# neonred-coded-update-2026-10-06.net
KiCad netlist of a schematic drawn in EasyEDA
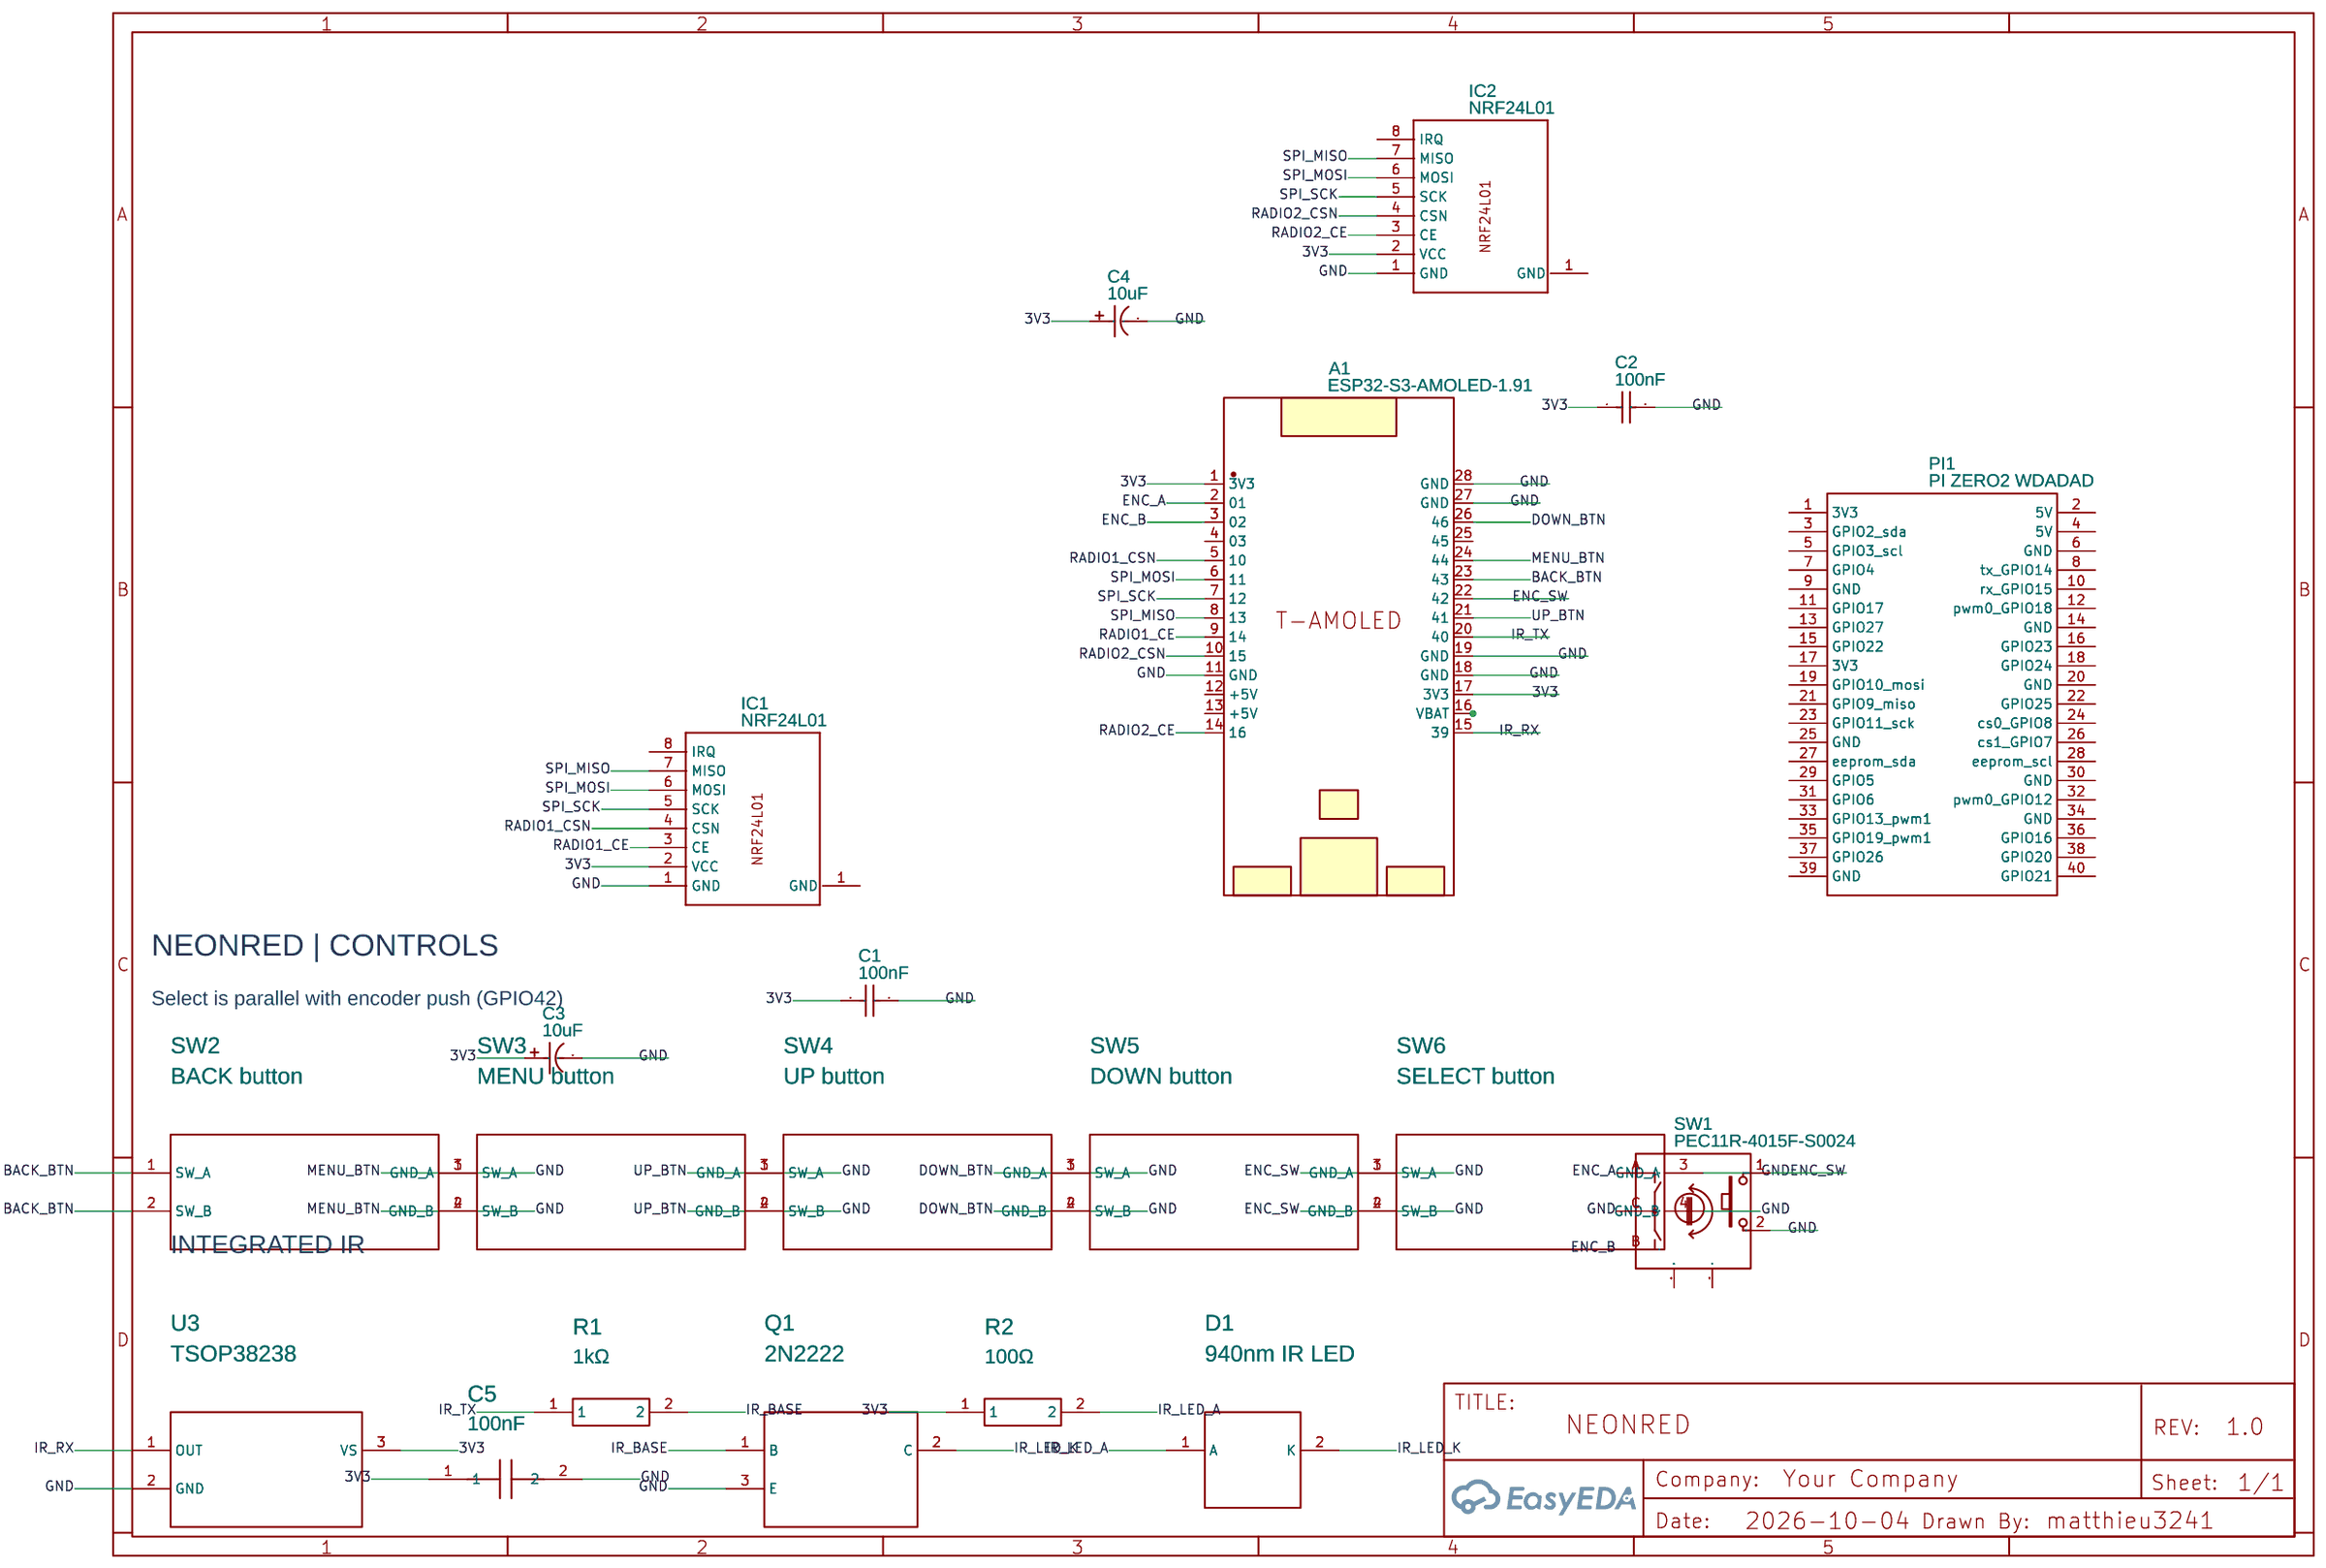
[diagram p0: schematic sheet]

(export (version "E")
  (design (tool "Eeschema 10.0.6"))
  (components
    (comp (ref "A1")
      (value "ESP32-S3-AMOLED-1.91")
      (fields (field (name "Manufacturer Part") "T-Display S3 AMOLED") (field (name "Manufacturer") "Lilygo"))
      (libsource (lib "") (part "ESP32-S3-AMOLED-1.91"))
    )
    (comp (ref "C1")
      (value "100nF")
      (fields (field (name "Manufacturer Part") "0.1UF(104) +-20% 63v"))
      (libsource (lib "") (part "100nF"))
    )
    (comp (ref "C2")
      (value "100nF")
      (fields (field (name "Manufacturer Part") "0.1UF(104) +-20% 63v"))
      (libsource (lib "") (part "100nF"))
    )
    (comp (ref "C3") (value "10uF") (libsource (lib "") (part "Capacitor 10uF TH")))
    (comp (ref "C4") (value "10uF") (libsource (lib "") (part "Capacitor 10uF TH")))
    (comp (ref "C5")
      (value "100nF")
      (fields (field (name "Manufacturer Part") "100nF ceramic THT"))
      (libsource (lib "") (part "100nF_1"))
    )
    (comp (ref "D1")
      (value "940nm IR LED")
      (fields (field (name "Manufacturer Part") "940nm IR LED, 5 mm THT"))
      (libsource (lib "") (part "940nm IR LED"))
    )
    (comp (ref "IC1") (value "NRF24L01") (libsource (lib "") (part "NRF24L01")))
    (comp (ref "IC2") (value "NRF24L01") (libsource (lib "") (part "NRF24L01")))
    (comp (ref "PI1") (value "PI ZERO2 WDADAD") (libsource (lib "") (part "PI ZERO2 WDADAD")))
    (comp (ref "Q1")
      (value "2N2222")
      (fields (field (name "Manufacturer Part") "2N2222A"))
      (libsource (lib "") (part "2N2222"))
    )
    (comp (ref "R1")
      (value "1kΩ")
      (fields (field (name "Manufacturer Part") "1k axial THT"))
      (libsource (lib "") (part "1kΩ"))
    )
    (comp (ref "R2")
      (value "100Ω")
      (fields (field (name "Manufacturer Part") "100Ω axial THT"))
      (libsource (lib "") (part "100Ω"))
    )
    (comp (ref "SW1")
      (value "PEC11R-4015F-S0024")
      (fields (field (name "Manufacturer") "BOURNS"))
      (libsource (lib "") (part "PEC11R-4015F-S0024"))
    )
    (comp (ref "SW2")
      (value "BACK button")
      (fields (field (name "Manufacturer Part") "6x6mm THT tactile switch, NO"))
      (libsource (lib "") (part "BACK button"))
    )
    (comp (ref "SW3")
      (value "MENU button")
      (fields (field (name "Manufacturer Part") "6x6mm THT tactile switch, NO"))
      (libsource (lib "") (part "MENU button"))
    )
    (comp (ref "SW4")
      (value "UP button")
      (fields (field (name "Manufacturer Part") "6x6mm THT tactile switch, NO"))
      (libsource (lib "") (part "UP button"))
    )
    (comp (ref "SW5")
      (value "DOWN button")
      (fields (field (name "Manufacturer Part") "6x6mm THT tactile switch, NO"))
      (libsource (lib "") (part "DOWN button"))
    )
    (comp (ref "SW6")
      (value "SELECT button")
      (fields (field (name "Manufacturer Part") "6x6mm THT tactile switch, NO"))
      (libsource (lib "") (part "SELECT button"))
    )
    (comp (ref "U3") (value "TSOP38238") (libsource (lib "") (part "TSOP38238")))
  )
  (nets
    (net (code "1") (name "/3V3") (class "Default")
      (node (ref "A1") (pin "1") (pinfunction "3V3_1") (pintype "unspecified"))
      (node (ref "A1") (pin "17") (pinfunction "3V3_17") (pintype "unspecified"))
      (node (ref "C1") (pin "1") (pinfunction "1_1") (pintype "input"))
      (node (ref "C2") (pin "1") (pinfunction "1_1") (pintype "input"))
      (node (ref "C3") (pin "1") (pinfunction "1_1") (pintype "input"))
      (node (ref "C4") (pin "1") (pinfunction "1_1") (pintype "input"))
      (node (ref "C5") (pin "1") (pinfunction "1_1") (pintype "unspecified"))
      (node (ref "IC1") (pin "2") (pinfunction "VCC_2") (pintype "bidirectional"))
      (node (ref "IC2") (pin "2") (pinfunction "VCC_2") (pintype "bidirectional"))
      (node (ref "R2") (pin "1") (pinfunction "1_1") (pintype "unspecified"))
      (node (ref "U3") (pin "3") (pinfunction "VS_3") (pintype "unspecified"))
    )
    (net (code "2") (name "/BACK_BTN") (class "Default")
      (node (ref "A1") (pin "23") (pinfunction "43_23") (pintype "unspecified"))
      (node (ref "SW2") (pin "1") (pinfunction "SW_A_1") (pintype "unspecified"))
      (node (ref "SW2") (pin "2") (pinfunction "SW_B_2") (pintype "unspecified"))
    )
    (net (code "3") (name "/DOWN_BTN") (class "Default")
      (node (ref "A1") (pin "26") (pinfunction "46_26") (pintype "unspecified"))
      (node (ref "SW5") (pin "1") (pinfunction "SW_A_1") (pintype "unspecified"))
      (node (ref "SW5") (pin "2") (pinfunction "SW_B_2") (pintype "unspecified"))
    )
    (net (code "4") (name "/ENC_A") (class "Default")
      (node (ref "A1") (pin "2") (pinfunction "01_2") (pintype "unspecified"))
      (node (ref "SW1") (pin "A") (pinfunction "A_A") (pintype "unspecified"))
    )
    (net (code "5") (name "/ENC_B") (class "Default")
      (node (ref "A1") (pin "3") (pinfunction "02_3") (pintype "unspecified"))
      (node (ref "SW1") (pin "B") (pinfunction "B_B") (pintype "unspecified"))
    )
    (net (code "6") (name "/ENC_SW") (class "Default")
      (node (ref "A1") (pin "22") (pinfunction "42_22") (pintype "unspecified"))
      (node (ref "SW1") (pin "1") (pinfunction "1_1") (pintype "unspecified"))
      (node (ref "SW6") (pin "1") (pinfunction "SW_A_1") (pintype "unspecified"))
      (node (ref "SW6") (pin "2") (pinfunction "SW_B_2") (pintype "unspecified"))
    )
    (net (code "7") (name "/GND") (class "Default")
      (node (ref "A1") (pin "11") (pinfunction "GND_11") (pintype "unspecified"))
      (node (ref "A1") (pin "18") (pinfunction "GND_18") (pintype "unspecified"))
      (node (ref "A1") (pin "19") (pinfunction "GND_19") (pintype "unspecified"))
      (node (ref "A1") (pin "27") (pinfunction "GND_27") (pintype "unspecified"))
      (node (ref "A1") (pin "28") (pinfunction "GND_28") (pintype "unspecified"))
      (node (ref "C1") (pin "2") (pinfunction "2_2") (pintype "input"))
      (node (ref "C2") (pin "2") (pinfunction "2_2") (pintype "input"))
      (node (ref "C3") (pin "2") (pinfunction "2_2") (pintype "input"))
      (node (ref "C4") (pin "2") (pinfunction "2_2") (pintype "input"))
      (node (ref "C5") (pin "2") (pinfunction "2_2") (pintype "unspecified"))
      (node (ref "IC1") (pin "1") (pinfunction "GND_1") (pintype "bidirectional"))
      (node (ref "IC2") (pin "1") (pinfunction "GND_1") (pintype "bidirectional"))
      (node (ref "Q1") (pin "3") (pinfunction "E_3") (pintype "unspecified"))
      (node (ref "SW1") (pin "2") (pinfunction "2_2") (pintype "unspecified"))
      (node (ref "SW1") (pin "C") (pinfunction "C_C") (pintype "unspecified"))
      (node (ref "SW2") (pin "3") (pinfunction "GND_A_3") (pintype "unspecified"))
      (node (ref "SW2") (pin "4") (pinfunction "GND_B_4") (pintype "unspecified"))
      (node (ref "SW3") (pin "3") (pinfunction "GND_A_3") (pintype "unspecified"))
      (node (ref "SW3") (pin "4") (pinfunction "GND_B_4") (pintype "unspecified"))
      (node (ref "SW4") (pin "3") (pinfunction "GND_A_3") (pintype "unspecified"))
      (node (ref "SW4") (pin "4") (pinfunction "GND_B_4") (pintype "unspecified"))
      (node (ref "SW5") (pin "3") (pinfunction "GND_A_3") (pintype "unspecified"))
      (node (ref "SW5") (pin "4") (pinfunction "GND_B_4") (pintype "unspecified"))
      (node (ref "SW6") (pin "3") (pinfunction "GND_A_3") (pintype "unspecified"))
      (node (ref "SW6") (pin "4") (pinfunction "GND_B_4") (pintype "unspecified"))
      (node (ref "U3") (pin "2") (pinfunction "GND_2") (pintype "unspecified"))
    )
    (net (code "8") (name "/IR_BASE") (class "Default")
      (node (ref "Q1") (pin "1") (pinfunction "B_1") (pintype "unspecified"))
      (node (ref "R1") (pin "2") (pinfunction "2_2") (pintype "unspecified"))
    )
    (net (code "9") (name "/IR_LED_A") (class "Default")
      (node (ref "D1") (pin "1") (pinfunction "A_1") (pintype "unspecified"))
      (node (ref "R2") (pin "2") (pinfunction "2_2") (pintype "unspecified"))
    )
    (net (code "10") (name "/IR_LED_K") (class "Default")
      (node (ref "D1") (pin "2") (pinfunction "K_2") (pintype "unspecified"))
      (node (ref "Q1") (pin "2") (pinfunction "C_2") (pintype "unspecified"))
    )
    (net (code "11") (name "/IR_RX") (class "Default")
      (node (ref "A1") (pin "15") (pinfunction "39_15") (pintype "unspecified"))
      (node (ref "U3") (pin "1") (pinfunction "OUT_1") (pintype "unspecified"))
    )
    (net (code "12") (name "/IR_TX") (class "Default")
      (node (ref "A1") (pin "20") (pinfunction "40_20") (pintype "unspecified"))
      (node (ref "R1") (pin "1") (pinfunction "1_1") (pintype "unspecified"))
    )
    (net (code "13") (name "/MENU_BTN") (class "Default")
      (node (ref "A1") (pin "24") (pinfunction "44_24") (pintype "unspecified"))
      (node (ref "SW3") (pin "1") (pinfunction "SW_A_1") (pintype "unspecified"))
      (node (ref "SW3") (pin "2") (pinfunction "SW_B_2") (pintype "unspecified"))
    )
    (net (code "14") (name "/RADIO1_CE") (class "Default")
      (node (ref "A1") (pin "9") (pinfunction "14_9") (pintype "unspecified"))
      (node (ref "IC1") (pin "3") (pinfunction "CE_3") (pintype "bidirectional"))
    )
    (net (code "15") (name "/RADIO1_CSN") (class "Default")
      (node (ref "A1") (pin "5") (pinfunction "10_5") (pintype "unspecified"))
      (node (ref "IC1") (pin "4") (pinfunction "CSN_4") (pintype "bidirectional"))
    )
    (net (code "16") (name "/RADIO2_CE") (class "Default")
      (node (ref "A1") (pin "14") (pinfunction "16_14") (pintype "unspecified"))
      (node (ref "IC2") (pin "3") (pinfunction "CE_3") (pintype "bidirectional"))
    )
    (net (code "17") (name "/RADIO2_CSN") (class "Default")
      (node (ref "A1") (pin "10") (pinfunction "15_10") (pintype "unspecified"))
      (node (ref "IC2") (pin "4") (pinfunction "CSN_4") (pintype "bidirectional"))
    )
    (net (code "18") (name "/SPI_MISO") (class "Default")
      (node (ref "A1") (pin "8") (pinfunction "13_8") (pintype "unspecified"))
      (node (ref "IC1") (pin "7") (pinfunction "MISO_7") (pintype "bidirectional"))
      (node (ref "IC2") (pin "7") (pinfunction "MISO_7") (pintype "bidirectional"))
    )
    (net (code "19") (name "/SPI_MOSI") (class "Default")
      (node (ref "A1") (pin "6") (pinfunction "11_6") (pintype "unspecified"))
      (node (ref "IC1") (pin "6") (pinfunction "MOSI_6") (pintype "bidirectional"))
      (node (ref "IC2") (pin "6") (pinfunction "MOSI_6") (pintype "bidirectional"))
    )
    (net (code "20") (name "/SPI_SCK") (class "Default")
      (node (ref "A1") (pin "7") (pinfunction "12_7") (pintype "unspecified"))
      (node (ref "IC1") (pin "5") (pinfunction "SCK_5") (pintype "bidirectional"))
      (node (ref "IC2") (pin "5") (pinfunction "SCK_5") (pintype "bidirectional"))
    )
    (net (code "21") (name "/UP_BTN") (class "Default")
      (node (ref "A1") (pin "21") (pinfunction "41_21") (pintype "unspecified"))
      (node (ref "SW4") (pin "1") (pinfunction "SW_A_1") (pintype "unspecified"))
      (node (ref "SW4") (pin "2") (pinfunction "SW_B_2") (pintype "unspecified"))
    )
    (net (code "22") (name "unconnected-(A1-+5V-Pad12)") (class "Default")
      (node (ref "A1") (pin "12") (pinfunction "+5V_12") (pintype "unspecified"))
    )
    (net (code "23") (name "unconnected-(A1-+5V-Pad13)") (class "Default")
      (node (ref "A1") (pin "13") (pinfunction "+5V_13") (pintype "unspecified"))
    )
    (net (code "24") (name "unconnected-(A1-03-Pad4)") (class "Default")
      (node (ref "A1") (pin "4") (pinfunction "03_4") (pintype "unspecified"))
    )
    (net (code "25") (name "unconnected-(A1-45-Pad25)") (class "Default")
      (node (ref "A1") (pin "25") (pinfunction "45_25") (pintype "unspecified"))
    )
    (net (code "26") (name "unconnected-(A1-VBAT-Pad16)") (class "Default")
      (node (ref "A1") (pin "16") (pinfunction "VBAT_16") (pintype "unspecified"))
    )
    (net (code "27") (name "unconnected-(IC1-GND-Pad1)") (class "Default")
      (node (ref "IC1") (pin "1") (pinfunction "GND_1") (pintype "bidirectional"))
    )
    (net (code "28") (name "unconnected-(IC1-IRQ-Pad8)") (class "Default")
      (node (ref "IC1") (pin "8") (pinfunction "IRQ_8") (pintype "bidirectional"))
    )
    (net (code "29") (name "unconnected-(IC2-GND-Pad1)") (class "Default")
      (node (ref "IC2") (pin "1") (pinfunction "GND_1") (pintype "bidirectional"))
    )
    (net (code "30") (name "unconnected-(IC2-IRQ-Pad8)") (class "Default")
      (node (ref "IC2") (pin "8") (pinfunction "IRQ_8") (pintype "bidirectional"))
    )
    (net (code "31") (name "unconnected-(PI1-3V3-Pad1)") (class "Default")
      (node (ref "PI1") (pin "1") (pinfunction "3V3_1") (pintype "unspecified"))
    )
    (net (code "32") (name "unconnected-(PI1-3V3-Pad17)") (class "Default")
      (node (ref "PI1") (pin "17") (pinfunction "3V3_17") (pintype "unspecified"))
    )
    (net (code "33") (name "unconnected-(PI1-5V-Pad2)") (class "Default")
      (node (ref "PI1") (pin "2") (pinfunction "5V_2") (pintype "unspecified"))
    )
    (net (code "34") (name "unconnected-(PI1-5V-Pad4)") (class "Default")
      (node (ref "PI1") (pin "4") (pinfunction "5V_4") (pintype "unspecified"))
    )
    (net (code "35") (name "unconnected-(PI1-GND-Pad6)") (class "Default")
      (node (ref "PI1") (pin "6") (pinfunction "GND_6") (pintype "unspecified"))
    )
    (net (code "36") (name "unconnected-(PI1-GND-Pad9)") (class "Default")
      (node (ref "PI1") (pin "9") (pinfunction "GND_9") (pintype "unspecified"))
    )
    (net (code "37") (name "unconnected-(PI1-GND-Pad14)") (class "Default")
      (node (ref "PI1") (pin "14") (pinfunction "GND_14") (pintype "unspecified"))
    )
    (net (code "38") (name "unconnected-(PI1-GND-Pad20)") (class "Default")
      (node (ref "PI1") (pin "20") (pinfunction "GND_20") (pintype "unspecified"))
    )
    (net (code "39") (name "unconnected-(PI1-GND-Pad25)") (class "Default")
      (node (ref "PI1") (pin "25") (pinfunction "GND_25") (pintype "unspecified"))
    )
    (net (code "40") (name "unconnected-(PI1-GND-Pad30)") (class "Default")
      (node (ref "PI1") (pin "30") (pinfunction "GND_30") (pintype "unspecified"))
    )
    (net (code "41") (name "unconnected-(PI1-GND-Pad34)") (class "Default")
      (node (ref "PI1") (pin "34") (pinfunction "GND_34") (pintype "unspecified"))
    )
    (net (code "42") (name "unconnected-(PI1-GND-Pad39)") (class "Default")
      (node (ref "PI1") (pin "39") (pinfunction "GND_39") (pintype "unspecified"))
    )
    (net (code "43") (name "unconnected-(PI1-GPIO2_sda-Pad3)") (class "Default")
      (node (ref "PI1") (pin "3") (pinfunction "GPIO2_sda_3") (pintype "unspecified"))
    )
    (net (code "44") (name "unconnected-(PI1-GPIO3_scl-Pad5)") (class "Default")
      (node (ref "PI1") (pin "5") (pinfunction "GPIO3_scl_5") (pintype "unspecified"))
    )
    (net (code "45") (name "unconnected-(PI1-GPIO4-Pad7)") (class "Default")
      (node (ref "PI1") (pin "7") (pinfunction "GPIO4_7") (pintype "unspecified"))
    )
    (net (code "46") (name "unconnected-(PI1-GPIO5-Pad29)") (class "Default")
      (node (ref "PI1") (pin "29") (pinfunction "GPIO5_29") (pintype "unspecified"))
    )
    (net (code "47") (name "unconnected-(PI1-GPIO6-Pad31)") (class "Default")
      (node (ref "PI1") (pin "31") (pinfunction "GPIO6_31") (pintype "unspecified"))
    )
    (net (code "48") (name "unconnected-(PI1-GPIO9_miso-Pad21)") (class "Default")
      (node (ref "PI1") (pin "21") (pinfunction "GPIO9_miso_21") (pintype "unspecified"))
    )
    (net (code "49") (name "unconnected-(PI1-GPIO10_mosi-Pad19)") (class "Default")
      (node (ref "PI1") (pin "19") (pinfunction "GPIO10_mosi_19") (pintype "unspecified"))
    )
    (net (code "50") (name "unconnected-(PI1-GPIO11_sck-Pad23)") (class "Default")
      (node (ref "PI1") (pin "23") (pinfunction "GPIO11_sck_23") (pintype "unspecified"))
    )
    (net (code "51") (name "unconnected-(PI1-GPIO13_pwm1-Pad33)") (class "Default")
      (node (ref "PI1") (pin "33") (pinfunction "GPIO13_pwm1_33") (pintype "unspecified"))
    )
    (net (code "52") (name "unconnected-(PI1-GPIO16-Pad36)") (class "Default")
      (node (ref "PI1") (pin "36") (pinfunction "GPIO16_36") (pintype "unspecified"))
    )
    (net (code "53") (name "unconnected-(PI1-GPIO17-Pad11)") (class "Default")
      (node (ref "PI1") (pin "11") (pinfunction "GPIO17_11") (pintype "unspecified"))
    )
    (net (code "54") (name "unconnected-(PI1-GPIO19_pwm1-Pad35)") (class "Default")
      (node (ref "PI1") (pin "35") (pinfunction "GPIO19_pwm1_35") (pintype "unspecified"))
    )
    (net (code "55") (name "unconnected-(PI1-GPIO20-Pad38)") (class "Default")
      (node (ref "PI1") (pin "38") (pinfunction "GPIO20_38") (pintype "unspecified"))
    )
    (net (code "56") (name "unconnected-(PI1-GPIO21-Pad40)") (class "Default")
      (node (ref "PI1") (pin "40") (pinfunction "GPIO21_40") (pintype "unspecified"))
    )
    (net (code "57") (name "unconnected-(PI1-GPIO22-Pad15)") (class "Default")
      (node (ref "PI1") (pin "15") (pinfunction "GPIO22_15") (pintype "unspecified"))
    )
    (net (code "58") (name "unconnected-(PI1-GPIO23-Pad16)") (class "Default")
      (node (ref "PI1") (pin "16") (pinfunction "GPIO23_16") (pintype "unspecified"))
    )
    (net (code "59") (name "unconnected-(PI1-GPIO24-Pad18)") (class "Default")
      (node (ref "PI1") (pin "18") (pinfunction "GPIO24_18") (pintype "unspecified"))
    )
    (net (code "60") (name "unconnected-(PI1-GPIO25-Pad22)") (class "Default")
      (node (ref "PI1") (pin "22") (pinfunction "GPIO25_22") (pintype "unspecified"))
    )
    (net (code "61") (name "unconnected-(PI1-GPIO26-Pad37)") (class "Default")
      (node (ref "PI1") (pin "37") (pinfunction "GPIO26_37") (pintype "unspecified"))
    )
    (net (code "62") (name "unconnected-(PI1-GPIO27-Pad13)") (class "Default")
      (node (ref "PI1") (pin "13") (pinfunction "GPIO27_13") (pintype "unspecified"))
    )
    (net (code "63") (name "unconnected-(PI1-cs0_GPIO8-Pad24)") (class "Default")
      (node (ref "PI1") (pin "24") (pinfunction "cs0_GPIO8_24") (pintype "unspecified"))
    )
    (net (code "64") (name "unconnected-(PI1-cs1_GPIO7-Pad26)") (class "Default")
      (node (ref "PI1") (pin "26") (pinfunction "cs1_GPIO7_26") (pintype "unspecified"))
    )
    (net (code "65") (name "unconnected-(PI1-eeprom_scl-Pad28)") (class "Default")
      (node (ref "PI1") (pin "28") (pinfunction "eeprom_scl_28") (pintype "unspecified"))
    )
    (net (code "66") (name "unconnected-(PI1-eeprom_sda-Pad27)") (class "Default")
      (node (ref "PI1") (pin "27") (pinfunction "eeprom_sda_27") (pintype "unspecified"))
    )
    (net (code "67") (name "unconnected-(PI1-pwm0_GPIO12-Pad32)") (class "Default")
      (node (ref "PI1") (pin "32") (pinfunction "pwm0_GPIO12_32") (pintype "unspecified"))
    )
    (net (code "68") (name "unconnected-(PI1-pwm0_GPIO18-Pad12)") (class "Default")
      (node (ref "PI1") (pin "12") (pinfunction "pwm0_GPIO18_12") (pintype "unspecified"))
    )
    (net (code "69") (name "unconnected-(PI1-rx_GPIO15-Pad10)") (class "Default")
      (node (ref "PI1") (pin "10") (pinfunction "rx_GPIO15_10") (pintype "unspecified"))
    )
    (net (code "70") (name "unconnected-(PI1-tx_GPIO14-Pad8)") (class "Default")
      (node (ref "PI1") (pin "8") (pinfunction "tx_GPIO14_8") (pintype "unspecified"))
    )
    (net (code "71") (name "unconnected-(SW1-PadMT1)") (class "Default")
      (node (ref "SW1") (pin "MT1") (pinfunction "MT1_MT1") (pintype "unspecified"))
    )
    (net (code "72") (name "unconnected-(SW1-PadMT2)") (class "Default")
      (node (ref "SW1") (pin "MT2") (pinfunction "MT2_MT2") (pintype "unspecified"))
    )
  )
)
